# MPU-GPS.net
KiCad netlist of a schematic drawn in Altium Designer
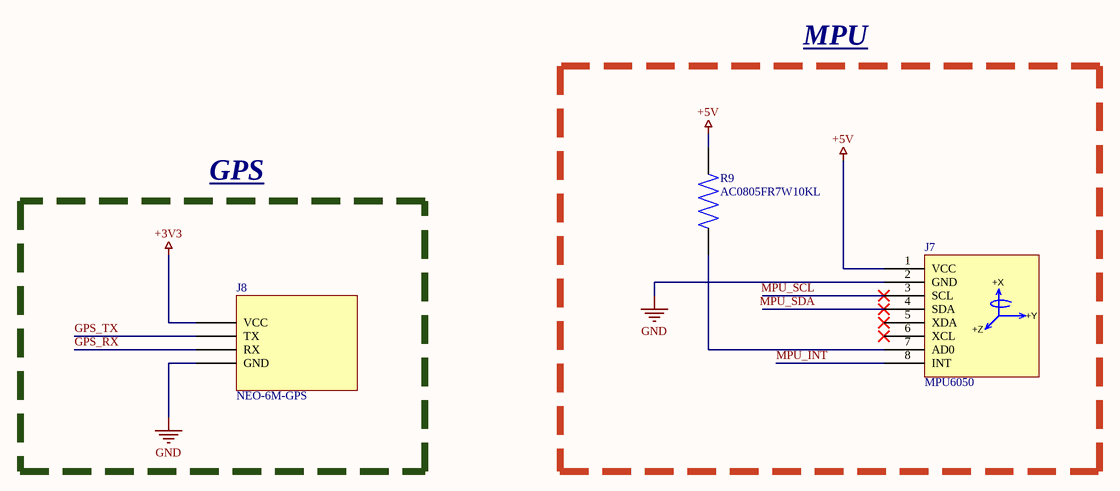
[diagram p0: MPU-GPS.SchDoc]

(export (version "E")
  (design (tool "Eeschema 10.0.6"))
  (components
    (comp (ref "J7") (value "MPU6050") (footprint "MPU6050") (libsource (lib "MySCH") (part "MPU6050")))
    (comp (ref "J8")
      (value "NEO-6M-GPS")
      (footprint "NEO-6M-GPS")
      (fields (field (name "MANUFACTURER") "u-blox"))
      (libsource (lib "MySCH") (part "NEO-6M-GPS"))
    )
    (comp (ref "R9")
      (value "AC0805FR7W10KL")
      (footprint "AC0805FR7W10KL:RESC2012X60N")
      (description "RES SMD 18 OHM 5% 1/8W 0805")
      (fields (field (name "MF") "{'manufacturer': u'Yageo Corporation'}"))
      (libsource (lib "*") (part "AC0805FR7W10KL"))
    )
  )
  (nets
    (net (code "1") (name "+3V3") (class "Default")
      (node (ref "J8") (pin "3") (pinfunction "VCC_3") (pintype "passive"))
    )
    (net (code "2") (name "+5V") (class "Default")
      (node (ref "J7") (pin "1") (pinfunction "VCC_1") (pintype "passive"))
      (node (ref "R9") (pin "1") (pinfunction "1_1") (pintype "passive"))
    )
    (net (code "3") (name "/GPS_RX") (class "Default")
      (node (ref "J8") (pin "2") (pinfunction "RX_2") (pintype "passive"))
    )
    (net (code "4") (name "/GPS_TX") (class "Default")
      (node (ref "J8") (pin "1") (pinfunction "TX_1") (pintype "passive"))
    )
    (net (code "5") (name "/MPU_INT") (class "Default")
      (node (ref "J7") (pin "8") (pinfunction "INT_8") (pintype "passive"))
    )
    (net (code "6") (name "/MPU_SCL") (class "Default")
      (node (ref "J7") (pin "3") (pinfunction "SCL_3") (pintype "passive+no_connect"))
    )
    (net (code "7") (name "/MPU_SDA") (class "Default")
      (node (ref "J7") (pin "4") (pinfunction "SDA_4") (pintype "passive+no_connect"))
    )
    (net (code "8") (name "GND") (class "Default")
      (node (ref "J7") (pin "2") (pinfunction "GND_2") (pintype "passive"))
      (node (ref "J8") (pin "0") (pinfunction "GND_0") (pintype "passive"))
    )
    (net (code "9") (name "Net-(J7-AD0)") (class "Default")
      (node (ref "J7") (pin "7") (pinfunction "AD0_7") (pintype "passive"))
      (node (ref "R9") (pin "2") (pinfunction "2_2") (pintype "passive"))
    )
    (net (code "10") (name "unconnected-(J7-XCL-Pad6)") (class "Default")
      (node (ref "J7") (pin "6") (pinfunction "XCL_6") (pintype "passive+no_connect"))
    )
    (net (code "11") (name "unconnected-(J7-XDA-Pad5)") (class "Default")
      (node (ref "J7") (pin "5") (pinfunction "XDA_5") (pintype "passive+no_connect"))
    )
  )
)
